# SCH_6_Channel_Energy_Monitor_17-09-2023_.net
KiCad netlist of a schematic drawn in EasyEDA
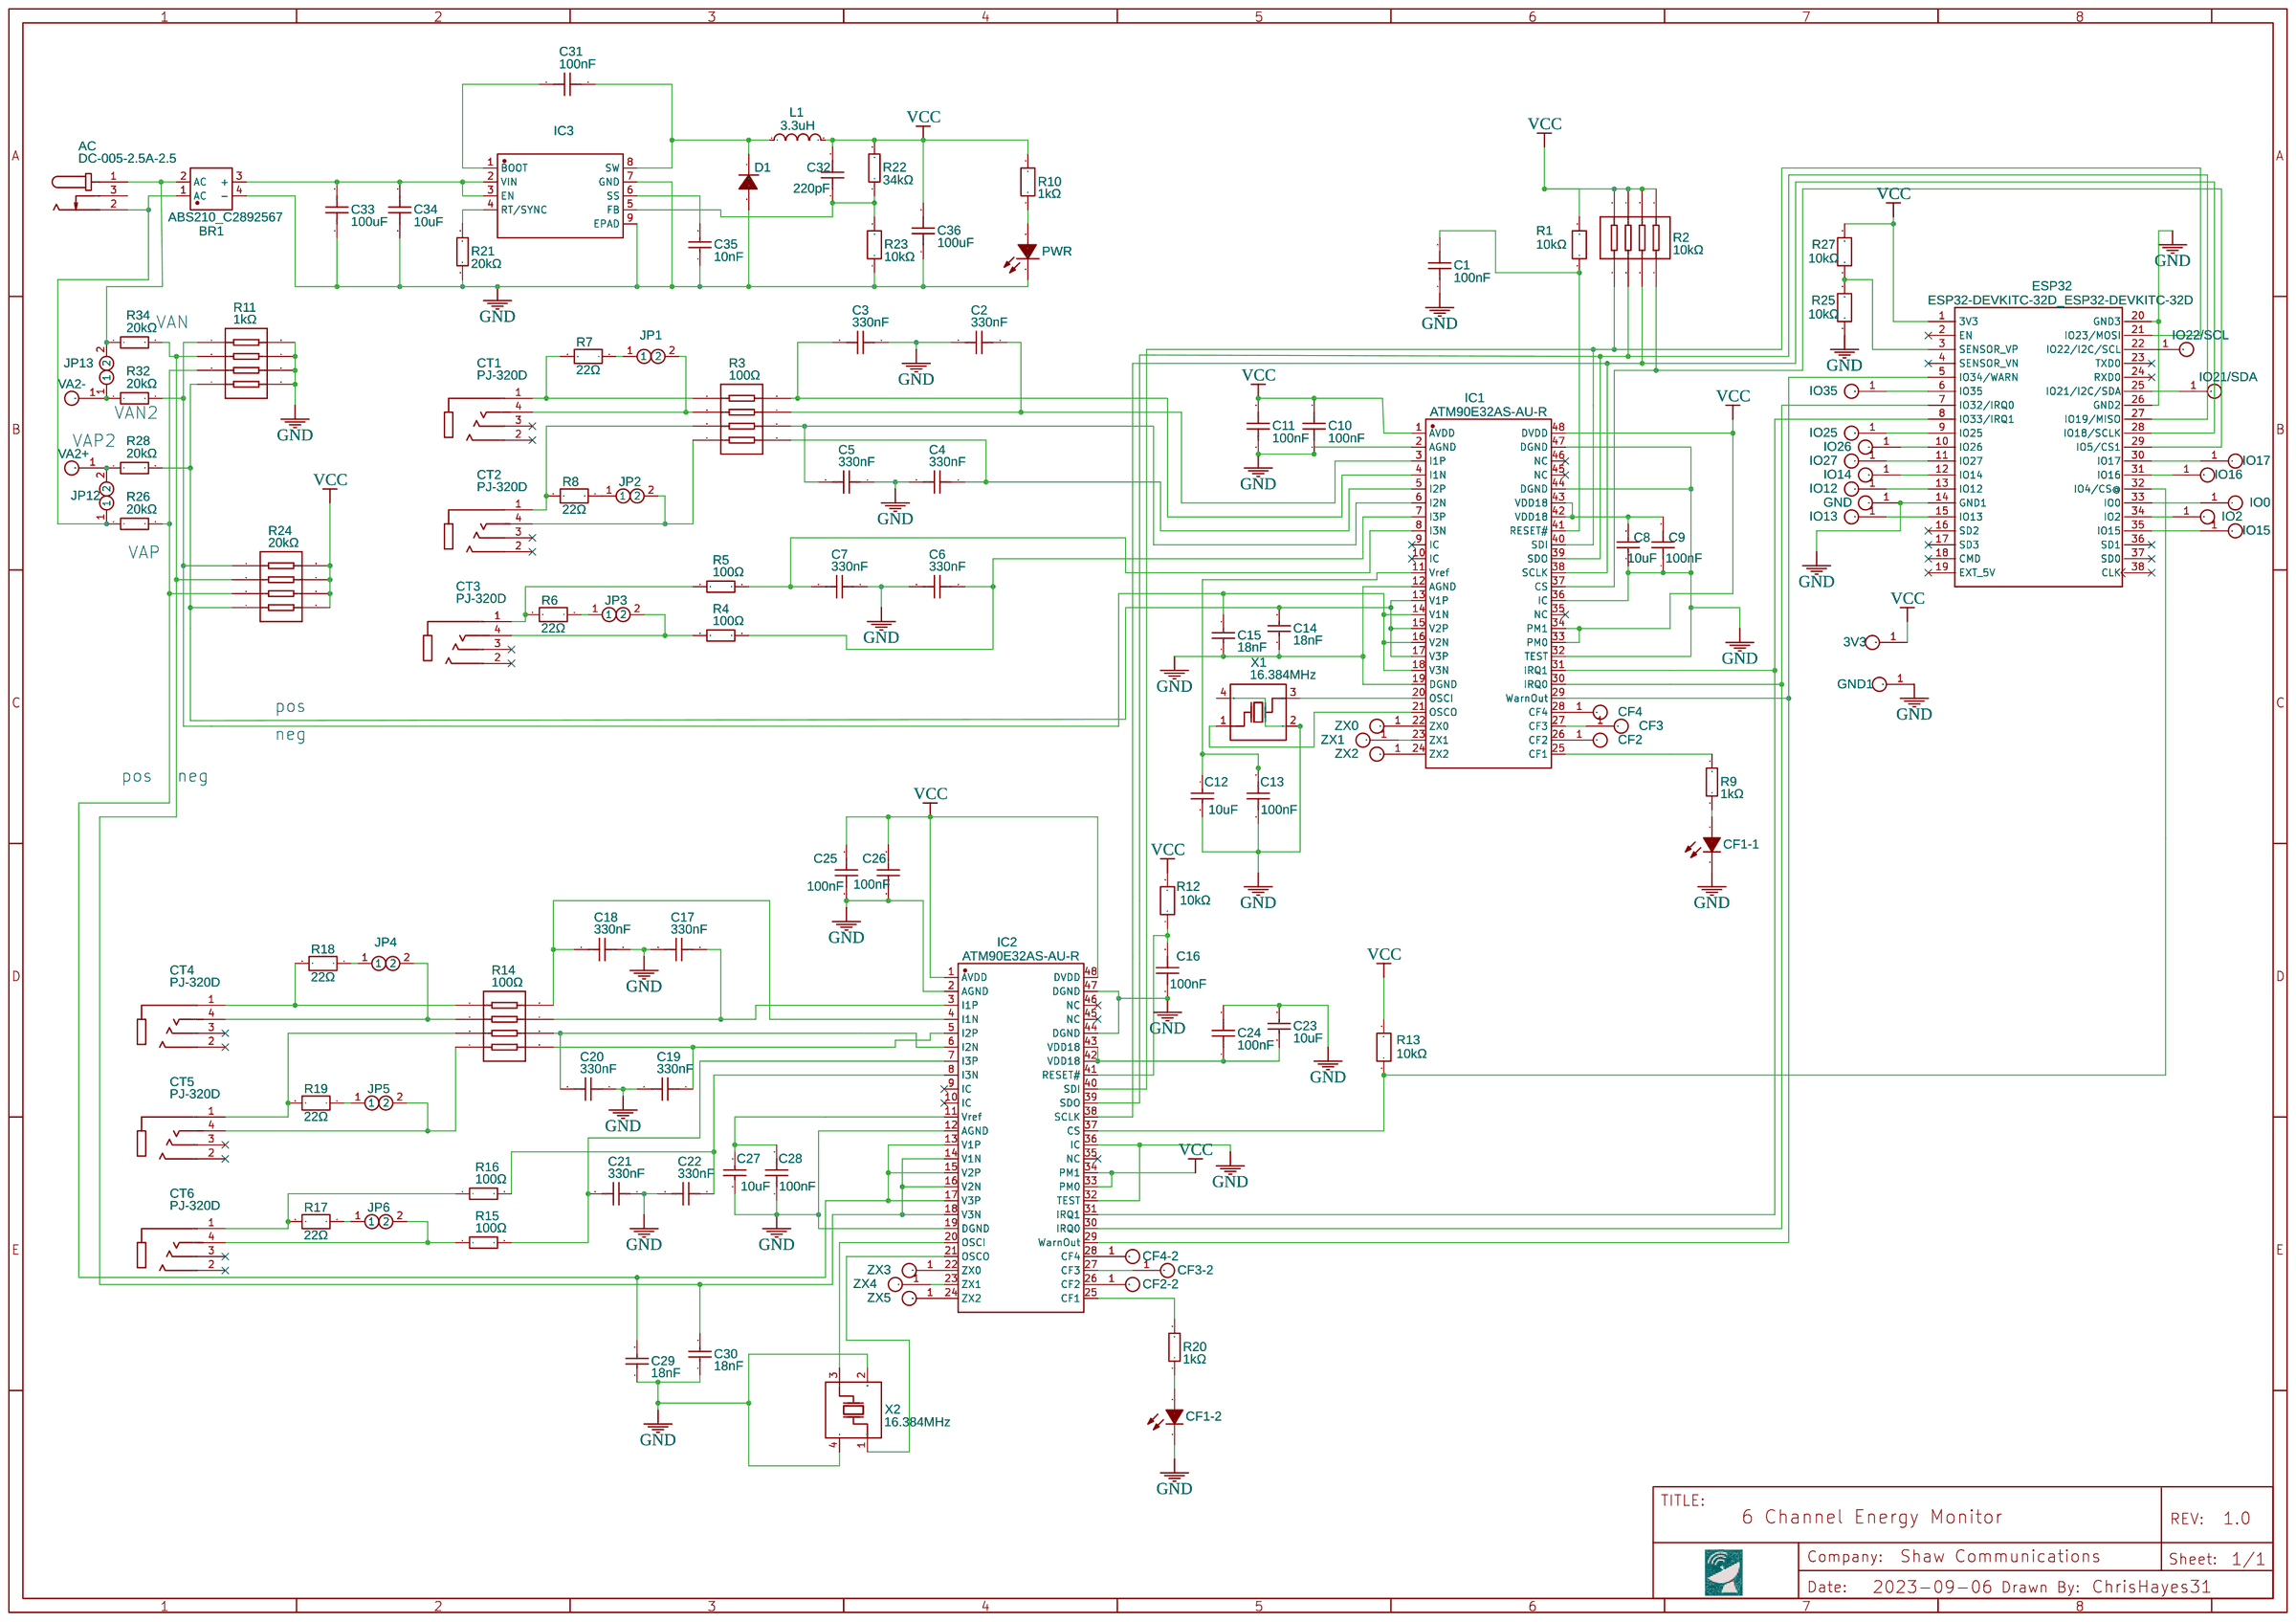
[diagram p0: schematic sheet]

(export (version "E")
  (design (tool "Eeschema 10.0.6"))
  (components
    (comp (ref "3V3") (value "PAD-ROUND") (libsource (lib "") (part "PAD-ROUND_12")))
    (comp (ref "AC")
      (value "DC-005-2.5A-2.5")
      (fields (field (name "Manufacturer") "XKB Enterprise"))
      (libsource (lib "") (part "DC-005-2.5A-2.5"))
    )
    (comp (ref "BR1")
      (value "ABS210_C2892567")
      (fields (field (name "Manufacturer Part") "ABS210") (field (name "Manufacturer") "YONGYUTAI(永裕泰)"))
      (libsource (lib "") (part "ABS210_C2892567"))
    )
    (comp (ref "C1")
      (value "100nF")
      (fields (field (name "Manufacturer Part") "CGJ4J2X7R1E104K125AA") (field (name "Manufacturer") "TDK"))
      (libsource (lib "") (part "CGJ4J2X7R1E104K125AA"))
    )
    (comp (ref "C2")
      (value "330nF")
      (fields
        (field (name "Manufacturer Part") "TCC0805X7R334K500DT")
        (field (name "Manufacturer") "CCTC(三环)")
      )
      (libsource (lib "") (part "TCC0805X7R334K500DT"))
    )
    (comp (ref "C3")
      (value "330nF")
      (fields
        (field (name "Manufacturer Part") "TCC0805X7R334K500DT")
        (field (name "Manufacturer") "CCTC(三环)")
      )
      (libsource (lib "") (part "TCC0805X7R334K500DT"))
    )
    (comp (ref "C4")
      (value "330nF")
      (fields
        (field (name "Manufacturer Part") "TCC0805X7R334K500DT")
        (field (name "Manufacturer") "CCTC(三环)")
      )
      (libsource (lib "") (part "TCC0805X7R334K500DT"))
    )
    (comp (ref "C5")
      (value "330nF")
      (fields
        (field (name "Manufacturer Part") "TCC0805X7R334K500DT")
        (field (name "Manufacturer") "CCTC(三环)")
      )
      (libsource (lib "") (part "TCC0805X7R334K500DT"))
    )
    (comp (ref "C6")
      (value "330nF")
      (fields
        (field (name "Manufacturer Part") "TCC0805X7R334K500DT")
        (field (name "Manufacturer") "CCTC(三环)")
      )
      (libsource (lib "") (part "TCC0805X7R334K500DT"))
    )
    (comp (ref "C7")
      (value "330nF")
      (fields
        (field (name "Manufacturer Part") "TCC0805X7R334K500DT")
        (field (name "Manufacturer") "CCTC(三环)")
      )
      (libsource (lib "") (part "TCC0805X7R334K500DT"))
    )
    (comp (ref "C8")
      (value "10uF")
      (fields
        (field (name "Manufacturer Part") "CC0805KKX5R8BB106")
        (field (name "Manufacturer") "YAGEO(国巨)")
      )
      (libsource (lib "") (part "CC0805KKX5R8BB106_1"))
    )
    (comp (ref "C9")
      (value "100nF")
      (fields (field (name "Manufacturer Part") "CGJ4J2X7R1E104K125AA") (field (name "Manufacturer") "TDK"))
      (libsource (lib "") (part "CGJ4J2X7R1E104K125AA"))
    )
    (comp (ref "C10")
      (value "100nF")
      (fields (field (name "Manufacturer Part") "CGJ4J2X7R1E104K125AA") (field (name "Manufacturer") "TDK"))
      (libsource (lib "") (part "CGJ4J2X7R1E104K125AA"))
    )
    (comp (ref "C11")
      (value "100nF")
      (fields (field (name "Manufacturer Part") "CGJ4J2X7R1E104K125AA") (field (name "Manufacturer") "TDK"))
      (libsource (lib "") (part "CGJ4J2X7R1E104K125AA"))
    )
    (comp (ref "C12")
      (value "10uF")
      (fields
        (field (name "Manufacturer Part") "CC0805KKX5R8BB106")
        (field (name "Manufacturer") "YAGEO(国巨)")
      )
      (libsource (lib "") (part "CC0805KKX5R8BB106"))
    )
    (comp (ref "C13")
      (value "100nF")
      (fields (field (name "Manufacturer Part") "CGJ4J2X7R1E104K125AA") (field (name "Manufacturer") "TDK"))
      (libsource (lib "") (part "CGJ4J2X7R1E104K125AA"))
    )
    (comp (ref "C14")
      (value "18nF")
      (fields
        (field (name "Manufacturer Part") "CC0805KRX7R9BB183")
        (field (name "Manufacturer") "YAGEO(国巨)")
      )
      (libsource (lib "") (part "CC0805KRX7R9BB183"))
    )
    (comp (ref "C15")
      (value "18nF")
      (fields
        (field (name "Manufacturer Part") "CC0805KRX7R9BB183")
        (field (name "Manufacturer") "YAGEO(国巨)")
      )
      (libsource (lib "") (part "CC0805KRX7R9BB183"))
    )
    (comp (ref "C16")
      (value "100nF")
      (fields (field (name "Manufacturer Part") "CGJ4J2X7R1E104K125AA") (field (name "Manufacturer") "TDK"))
      (libsource (lib "") (part "CGJ4J2X7R1E104K125AA"))
    )
    (comp (ref "C17")
      (value "330nF")
      (fields
        (field (name "Manufacturer Part") "TCC0805X7R334K500DT")
        (field (name "Manufacturer") "CCTC(三环)")
      )
      (libsource (lib "") (part "TCC0805X7R334K500DT"))
    )
    (comp (ref "C18")
      (value "330nF")
      (fields
        (field (name "Manufacturer Part") "TCC0805X7R334K500DT")
        (field (name "Manufacturer") "CCTC(三环)")
      )
      (libsource (lib "") (part "TCC0805X7R334K500DT"))
    )
    (comp (ref "C19")
      (value "330nF")
      (fields
        (field (name "Manufacturer Part") "TCC0805X7R334K500DT")
        (field (name "Manufacturer") "CCTC(三环)")
      )
      (libsource (lib "") (part "TCC0805X7R334K500DT"))
    )
    (comp (ref "C20")
      (value "330nF")
      (fields
        (field (name "Manufacturer Part") "TCC0805X7R334K500DT")
        (field (name "Manufacturer") "CCTC(三环)")
      )
      (libsource (lib "") (part "TCC0805X7R334K500DT"))
    )
    (comp (ref "C21")
      (value "330nF")
      (fields
        (field (name "Manufacturer Part") "TCC0805X7R334K500DT")
        (field (name "Manufacturer") "CCTC(三环)")
      )
      (libsource (lib "") (part "TCC0805X7R334K500DT"))
    )
    (comp (ref "C22")
      (value "330nF")
      (fields
        (field (name "Manufacturer Part") "TCC0805X7R334K500DT")
        (field (name "Manufacturer") "CCTC(三环)")
      )
      (libsource (lib "") (part "TCC0805X7R334K500DT"))
    )
    (comp (ref "C23")
      (value "10uF")
      (fields
        (field (name "Manufacturer Part") "CC0805KKX5R8BB106")
        (field (name "Manufacturer") "YAGEO(国巨)")
      )
      (libsource (lib "") (part "CC0805KKX5R8BB106_1"))
    )
    (comp (ref "C24")
      (value "100nF")
      (fields (field (name "Manufacturer Part") "CGJ4J2X7R1E104K125AA") (field (name "Manufacturer") "TDK"))
      (libsource (lib "") (part "CGJ4J2X7R1E104K125AA"))
    )
    (comp (ref "C25")
      (value "100nF")
      (fields (field (name "Manufacturer Part") "CGJ4J2X7R1E104K125AA") (field (name "Manufacturer") "TDK"))
      (libsource (lib "") (part "CGJ4J2X7R1E104K125AA"))
    )
    (comp (ref "C26")
      (value "100nF")
      (fields (field (name "Manufacturer Part") "CGJ4J2X7R1E104K125AA") (field (name "Manufacturer") "TDK"))
      (libsource (lib "") (part "CGJ4J2X7R1E104K125AA"))
    )
    (comp (ref "C27")
      (value "10uF")
      (fields
        (field (name "Manufacturer Part") "CC0805KKX5R8BB106")
        (field (name "Manufacturer") "YAGEO(国巨)")
      )
      (libsource (lib "") (part "CC0805KKX5R8BB106"))
    )
    (comp (ref "C28")
      (value "100nF")
      (fields (field (name "Manufacturer Part") "CGJ4J2X7R1E104K125AA") (field (name "Manufacturer") "TDK"))
      (libsource (lib "") (part "CGJ4J2X7R1E104K125AA"))
    )
    (comp (ref "C29")
      (value "18nF")
      (fields
        (field (name "Manufacturer Part") "CC0805KRX7R9BB183")
        (field (name "Manufacturer") "YAGEO(国巨)")
      )
      (libsource (lib "") (part "CC0805KRX7R9BB183"))
    )
    (comp (ref "C30")
      (value "18nF")
      (fields
        (field (name "Manufacturer Part") "CC0805KRX7R9BB183")
        (field (name "Manufacturer") "YAGEO(国巨)")
      )
      (libsource (lib "") (part "CC0805KRX7R9BB183"))
    )
    (comp (ref "C31")
      (value "100nF")
      (fields
        (field (name "Manufacturer Part") "CC0805JRX7R7BB104")
        (field (name "Manufacturer") "YAGEO(国巨)")
      )
      (libsource (lib "") (part "CC0805JRX7R7BB104"))
    )
    (comp (ref "C32")
      (value "220pF")
      (fields
        (field (name "Manufacturer Part") "CC0805JRNPO0BN221")
        (field (name "Manufacturer") "YAGEO(国巨)")
      )
      (libsource (lib "") (part "CC0805JRNPO0BN221"))
    )
    (comp (ref "C33")
      (value "100uF")
      (fields
        (field (name "Manufacturer Part") "GRM21BC80E107ME15L")
        (field (name "Manufacturer") "muRata(村田)")
      )
      (libsource (lib "") (part "GRM21BC80E107ME15L"))
    )
    (comp (ref "C34")
      (value "10uF")
      (fields
        (field (name "Manufacturer Part") "CC0805KKX7R7BB106")
        (field (name "Manufacturer") "YAGEO(国巨)")
      )
      (libsource (lib "") (part "CC0805KKX7R7BB106"))
    )
    (comp (ref "C35")
      (value "10nF")
      (fields
        (field (name "Manufacturer Part") "CC0805KKX7RBBB103")
        (field (name "Manufacturer") "YAGEO(国巨)")
      )
      (libsource (lib "") (part "CC0805KKX7RBBB103"))
    )
    (comp (ref "C36")
      (value "100uF")
      (fields
        (field (name "Manufacturer Part") "GRM21BC80E107ME15L")
        (field (name "Manufacturer") "muRata(村田)")
      )
      (libsource (lib "") (part "GRM21BC80E107ME15L"))
    )
    (comp (ref "CF1-1")
      (value "FC-DA1608BK-470H10")
      (fields (field (name "Manufacturer Part") "NCD0603B1") (field (name "Manufacturer") "国星光电"))
      (libsource (lib "") (part "FC-DA1608BK-470H10"))
    )
    (comp (ref "CF1-2")
      (value "FC-DA1608BK-470H10")
      (fields (field (name "Manufacturer Part") "NCD0603B1") (field (name "Manufacturer") "国星光电"))
      (libsource (lib "") (part "FC-DA1608BK-470H10"))
    )
    (comp (ref "CF2") (value "PAD-ROUND") (libsource (lib "") (part "PAD-ROUND_1")))
    (comp (ref "CF2-2") (value "PAD-ROUND") (libsource (lib "") (part "PAD-ROUND_11")))
    (comp (ref "CF3") (value "PAD-ROUND") (libsource (lib "") (part "PAD-ROUND_1")))
    (comp (ref "CF3-2") (value "PAD-ROUND") (libsource (lib "") (part "PAD-ROUND_8")))
    (comp (ref "CF4") (value "PAD-ROUND") (libsource (lib "") (part "PAD-ROUND_1")))
    (comp (ref "CF4-2") (value "PAD-ROUND") (libsource (lib "") (part "PAD-ROUND_10")))
    (comp (ref "CT1")
      (value "PJ-320D")
      (fields (field (name "Manufacturer") "SHOU HAN"))
      (libsource (lib "") (part "PJ-320D"))
    )
    (comp (ref "CT2")
      (value "PJ-320D")
      (fields (field (name "Manufacturer") "SHOU HAN"))
      (libsource (lib "") (part "PJ-320D"))
    )
    (comp (ref "CT3")
      (value "PJ-320D")
      (fields (field (name "Manufacturer") "SHOU HAN"))
      (libsource (lib "") (part "PJ-320D"))
    )
    (comp (ref "CT4")
      (value "PJ-320D")
      (fields (field (name "Manufacturer") "SHOU HAN"))
      (libsource (lib "") (part "PJ-320D"))
    )
    (comp (ref "CT5")
      (value "PJ-320D")
      (fields (field (name "Manufacturer") "SHOU HAN"))
      (libsource (lib "") (part "PJ-320D"))
    )
    (comp (ref "CT6")
      (value "PJ-320D")
      (fields (field (name "Manufacturer") "SHOU HAN"))
      (libsource (lib "") (part "PJ-320D"))
    )
    (comp (ref "D1")
      (value "M7_C95872")
      (fields (field (name "Manufacturer Part") "M7") (field (name "Manufacturer") "MDD"))
      (libsource (lib "") (part "M7_C95872"))
    )
    (comp (ref "ESP32")
      (value "ESP32-DEVKITC-32D_ESP32-DEVKITC-32D")
      (libsource (lib "") (part "ESP32-DEVKITC-32D_ESP32-DEVKITC-32D"))
    )
    (comp (ref "GND") (value "PAD-ROUND") (libsource (lib "") (part "PAD-ROUND_4")))
    (comp (ref "GND1") (value "PAD-ROUND") (libsource (lib "") (part "PAD-ROUND_4")))
    (comp (ref "IC1")
      (value "ATM90E32AS-AU-R")
      (fields (field (name "Manufacturer") "MICROCHIP(美国微芯)"))
      (libsource (lib "") (part "ATM90E32AS-AU-R"))
    )
    (comp (ref "IC2")
      (value "ATM90E32AS-AU-R")
      (fields (field (name "Manufacturer") "MICROCHIP(美国微芯)"))
      (libsource (lib "") (part "ATM90E32AS-AU-R"))
    )
    (comp (ref "IC3")
      (value "LMR14020SDDAR")
      (fields (field (name "Manufacturer") "TI(德州仪器)"))
      (libsource (lib "") (part "LMR14020SDDAR"))
    )
    (comp (ref "IO0") (value "PAD-ROUND") (libsource (lib "") (part "PAD-ROUND_2")))
    (comp (ref "IO2") (value "PAD-ROUND") (libsource (lib "") (part "PAD-ROUND_2")))
    (comp (ref "IO12") (value "PAD-ROUND") (libsource (lib "") (part "PAD-ROUND_5")))
    (comp (ref "IO13") (value "PAD-ROUND") (libsource (lib "") (part "PAD-ROUND_5")))
    (comp (ref "IO14") (value "PAD-ROUND") (libsource (lib "") (part "PAD-ROUND_5")))
    (comp (ref "IO15") (value "PAD-ROUND") (libsource (lib "") (part "PAD-ROUND_2")))
    (comp (ref "IO16") (value "PAD-ROUND") (libsource (lib "") (part "PAD-ROUND_2")))
    (comp (ref "IO17") (value "PAD-ROUND") (libsource (lib "") (part "PAD-ROUND_2")))
    (comp (ref "IO21/SDA") (value "PAD-ROUND") (libsource (lib "") (part "PAD-ROUND_3")))
    (comp (ref "IO22/SCL") (value "PAD-ROUND") (libsource (lib "") (part "PAD-ROUND_7")))
    (comp (ref "IO25") (value "PAD-ROUND") (libsource (lib "") (part "PAD-ROUND_5")))
    (comp (ref "IO26") (value "PAD-ROUND") (libsource (lib "") (part "PAD-ROUND_5")))
    (comp (ref "IO27") (value "PAD-ROUND") (libsource (lib "") (part "PAD-ROUND_5")))
    (comp (ref "IO35") (value "PAD-ROUND") (libsource (lib "") (part "PAD-ROUND_5")))
    (comp (ref "JP1") (value "J-pad soldering") (libsource (lib "") (part "J-pad soldering")))
    (comp (ref "JP2") (value "J-pad soldering") (libsource (lib "") (part "J-pad soldering")))
    (comp (ref "JP3") (value "J-pad soldering") (libsource (lib "") (part "J-pad soldering")))
    (comp (ref "JP4") (value "J-pad soldering") (libsource (lib "") (part "J-pad soldering")))
    (comp (ref "JP5") (value "J-pad soldering") (libsource (lib "") (part "J-pad soldering")))
    (comp (ref "JP6") (value "J-pad soldering") (libsource (lib "") (part "J-pad soldering")))
    (comp (ref "JP12") (value "J-pad soldering") (libsource (lib "") (part "J-pad soldering_1")))
    (comp (ref "JP13") (value "J-pad soldering") (libsource (lib "") (part "J-pad soldering_1")))
    (comp (ref "L1")
      (value "3.3uH")
      (fields (field (name "Manufacturer Part") "CYA0630-3.3UH") (field (name "Manufacturer") "SHOU HAN(首韩)"))
      (libsource (lib "") (part "CYA0630-3.3UH"))
    )
    (comp (ref "PWR")
      (value "EL0603/G6C-A01/DT(TS)(GW)")
      (fields (field (name "Manufacturer") "EVERLIGHT(亿光)"))
      (libsource (lib "") (part "EL0603/G6C-A01/DT(TS)(GW)"))
    )
    (comp (ref "R1")
      (value "10kΩ")
      (fields (field (name "Manufacturer Part") "SCR0805F10K") (field (name "Manufacturer") "VO(翔胜)"))
      (libsource (lib "") (part "SCR0805F10K"))
    )
    (comp (ref "R2")
      (value "10kΩ")
      (fields
        (field (name "Manufacturer Part") "4D03WGJ0103T5E")
        (field (name "Manufacturer") "UNI-ROYAL(厚声)")
      )
      (libsource (lib "") (part "4D03WGJ0103T5E"))
    )
    (comp (ref "R3")
      (value "100Ω")
      (fields
        (field (name "Manufacturer Part") "4D03WGJ0101T5E")
        (field (name "Manufacturer") "UNI-ROYAL(厚声)")
      )
      (libsource (lib "") (part "4D03WGJ0101T5E"))
    )
    (comp (ref "R4")
      (value "100Ω")
      (fields
        (field (name "Manufacturer Part") "0805W8F1000T5E")
        (field (name "Manufacturer") "UNI-ROYAL(厚声)")
      )
      (libsource (lib "") (part "0805W8F1000T5E"))
    )
    (comp (ref "R5")
      (value "100Ω")
      (fields
        (field (name "Manufacturer Part") "0805W8F1000T5E")
        (field (name "Manufacturer") "UNI-ROYAL(厚声)")
      )
      (libsource (lib "") (part "0805W8F1000T5E"))
    )
    (comp (ref "R6")
      (value "22Ω")
      (fields (field (name "Manufacturer Part") "SCR0805F22R") (field (name "Manufacturer") "VO(翔胜)"))
      (libsource (lib "") (part "SCR0805F22R"))
    )
    (comp (ref "R7")
      (value "22Ω")
      (fields (field (name "Manufacturer Part") "SCR0805F22R") (field (name "Manufacturer") "VO(翔胜)"))
      (libsource (lib "") (part "SCR0805F22R"))
    )
    (comp (ref "R8")
      (value "22Ω")
      (fields (field (name "Manufacturer Part") "SCR0805F22R") (field (name "Manufacturer") "VO(翔胜)"))
      (libsource (lib "") (part "SCR0805F22R"))
    )
    (comp (ref "R9")
      (value "1kΩ")
      (fields (field (name "Manufacturer Part") "CR0805F81001G") (field (name "Manufacturer") "LIZ(丽智电子)"))
      (libsource (lib "") (part "CR0805F81001G"))
    )
    (comp (ref "R10")
      (value "1kΩ")
      (fields (field (name "Manufacturer Part") "SCR0805F1K") (field (name "Manufacturer") "VO(翔胜)"))
      (libsource (lib "") (part "SCR0805F1K"))
    )
    (comp (ref "R11")
      (value "1kΩ")
      (fields
        (field (name "Manufacturer Part") "4D03WGJ0102T5E")
        (field (name "Manufacturer") "UNI-ROYAL(厚声)")
      )
      (libsource (lib "") (part "4D03WGJ0102T5E"))
    )
    (comp (ref "R12")
      (value "10kΩ")
      (fields (field (name "Manufacturer Part") "SCR0805F10K") (field (name "Manufacturer") "VO(翔胜)"))
      (libsource (lib "") (part "SCR0805F10K"))
    )
    (comp (ref "R13")
      (value "10kΩ")
      (fields (field (name "Manufacturer Part") "SCR0805F10K") (field (name "Manufacturer") "VO(翔胜)"))
      (libsource (lib "") (part "SCR0805F10K"))
    )
    (comp (ref "R14")
      (value "100Ω")
      (fields
        (field (name "Manufacturer Part") "4D03WGJ0101T5E")
        (field (name "Manufacturer") "UNI-ROYAL(厚声)")
      )
      (libsource (lib "") (part "4D03WGJ0101T5E"))
    )
    (comp (ref "R15")
      (value "100Ω")
      (fields
        (field (name "Manufacturer Part") "0805W8F1000T5E")
        (field (name "Manufacturer") "UNI-ROYAL(厚声)")
      )
      (libsource (lib "") (part "0805W8F1000T5E"))
    )
    (comp (ref "R16")
      (value "100Ω")
      (fields
        (field (name "Manufacturer Part") "0805W8F1000T5E")
        (field (name "Manufacturer") "UNI-ROYAL(厚声)")
      )
      (libsource (lib "") (part "0805W8F1000T5E"))
    )
    (comp (ref "R17")
      (value "22Ω")
      (fields (field (name "Manufacturer Part") "SCR0805F22R") (field (name "Manufacturer") "VO(翔胜)"))
      (libsource (lib "") (part "SCR0805F22R"))
    )
    (comp (ref "R18")
      (value "22Ω")
      (fields (field (name "Manufacturer Part") "SCR0805F22R") (field (name "Manufacturer") "VO(翔胜)"))
      (libsource (lib "") (part "SCR0805F22R"))
    )
    (comp (ref "R19")
      (value "22Ω")
      (fields (field (name "Manufacturer Part") "SCR0805F22R") (field (name "Manufacturer") "VO(翔胜)"))
      (libsource (lib "") (part "SCR0805F22R"))
    )
    (comp (ref "R20")
      (value "1kΩ")
      (fields (field (name "Manufacturer Part") "CR0805F81001G") (field (name "Manufacturer") "LIZ(丽智电子)"))
      (libsource (lib "") (part "CR0805F81001G"))
    )
    (comp (ref "R21")
      (value "20kΩ")
      (fields
        (field (name "Manufacturer Part") "QR0805F20K0P05Z")
        (field (name "Manufacturer") "EVER OHMS(天二科技)")
      )
      (libsource (lib "") (part "QR0805F20KP05"))
    )
    (comp (ref "R22")
      (value "34kΩ")
      (fields (field (name "Manufacturer Part") "AC0805FR-0734KL") (field (name "Manufacturer") "YAGEO(国巨)"))
      (libsource (lib "") (part "AC0805FR-0734KL"))
    )
    (comp (ref "R23")
      (value "10kΩ")
      (fields
        (field (name "Manufacturer Part") "CR0805J10K0P05Z")
        (field (name "Manufacturer") "EVER OHMS(天二科技)")
      )
      (libsource (lib "") (part "CR0805J10K0P05Z"))
    )
    (comp (ref "R24")
      (value "20kΩ")
      (fields
        (field (name "Manufacturer Part") "4D03WGJ0203T5E")
        (field (name "Manufacturer") "UNI-ROYAL(厚声)")
      )
      (libsource (lib "") (part "4D03WGJ0203T5E"))
    )
    (comp (ref "R25")
      (value "10kΩ")
      (fields (field (name "Manufacturer Part") "SCR0805F10K") (field (name "Manufacturer") "VO(翔胜)"))
      (libsource (lib "") (part "SCR0805F10K"))
    )
    (comp (ref "R26")
      (value "20kΩ")
      (fields (field (name "Manufacturer Part") "RK73H2ATTD2002F") (field (name "Manufacturer") "KOA"))
      (libsource (lib "") (part "RK73H2ATTD2002F"))
    )
    (comp (ref "R27")
      (value "10kΩ")
      (fields (field (name "Manufacturer Part") "SCR0805F10K") (field (name "Manufacturer") "VO(翔胜)"))
      (libsource (lib "") (part "SCR0805F10K"))
    )
    (comp (ref "R28")
      (value "20kΩ")
      (fields (field (name "Manufacturer Part") "RK73H2ATTD2002F") (field (name "Manufacturer") "KOA"))
      (libsource (lib "") (part "RK73H2ATTD2002F"))
    )
    (comp (ref "R32")
      (value "20kΩ")
      (fields (field (name "Manufacturer Part") "RK73H2ATTD2002F") (field (name "Manufacturer") "KOA"))
      (libsource (lib "") (part "RK73H2ATTD2002F"))
    )
    (comp (ref "R34")
      (value "20kΩ")
      (fields (field (name "Manufacturer Part") "RK73H2ATTD2002F") (field (name "Manufacturer") "KOA"))
      (libsource (lib "") (part "RK73H2ATTD2002F"))
    )
    (comp (ref "VA2+") (value "PAD-ROUND") (libsource (lib "") (part "PAD-ROUND_9")))
    (comp (ref "VA2-") (value "PAD-ROUND") (libsource (lib "") (part "PAD-ROUND_6")))
    (comp (ref "X1")
      (value "16.384MHz")
      (fields (field (name "Manufacturer Part") "X322516384MSB4SI") (field (name "Manufacturer") "YXC(扬兴晶振)"))
      (libsource (lib "") (part "X322516384MSB4SI"))
    )
    (comp (ref "X2")
      (value "16.384MHz")
      (fields (field (name "Manufacturer Part") "X322516384MSB4SI") (field (name "Manufacturer") "YXC(扬兴晶振)"))
      (libsource (lib "") (part "X322516384MSB4SI_1"))
    )
    (comp (ref "ZX0") (value "PAD-ROUND") (libsource (lib "") (part "PAD-ROUND")))
    (comp (ref "ZX1") (value "PAD-ROUND") (libsource (lib "") (part "PAD-ROUND")))
    (comp (ref "ZX2") (value "PAD-ROUND") (libsource (lib "") (part "PAD-ROUND")))
    (comp (ref "ZX3") (value "PAD-ROUND") (libsource (lib "") (part "PAD-ROUND")))
    (comp (ref "ZX4") (value "PAD-ROUND") (libsource (lib "") (part "PAD-ROUND")))
    (comp (ref "ZX5") (value "PAD-ROUND") (libsource (lib "") (part "PAD-ROUND")))
  )
  (nets
    (net (code "1") (name "GND") (class "Default")
      (node (ref "BR1") (pin "4") (pinfunction "-_4") (pintype "unspecified"))
      (node (ref "C1") (pin "1") (pinfunction "1_1") (pintype "unspecified"))
      (node (ref "C10") (pin "1") (pinfunction "1_1") (pintype "unspecified"))
      (node (ref "C11") (pin "1") (pinfunction "1_1") (pintype "unspecified"))
      (node (ref "C12") (pin "2") (pinfunction "2_2") (pintype "input"))
      (node (ref "C13") (pin "1") (pinfunction "1_1") (pintype "unspecified"))
      (node (ref "C14") (pin "1") (pinfunction "1_1") (pintype "input"))
      (node (ref "C15") (pin "1") (pinfunction "1_1") (pintype "input"))
      (node (ref "C16") (pin "1") (pinfunction "1_1") (pintype "unspecified"))
      (node (ref "C17") (pin "2") (pinfunction "2_2") (pintype "unspecified"))
      (node (ref "C18") (pin "1") (pinfunction "1_1") (pintype "unspecified"))
      (node (ref "C19") (pin "2") (pinfunction "2_2") (pintype "unspecified"))
      (node (ref "C2") (pin "2") (pinfunction "2_2") (pintype "unspecified"))
      (node (ref "C20") (pin "1") (pinfunction "1_1") (pintype "unspecified"))
      (node (ref "C21") (pin "1") (pinfunction "1_1") (pintype "unspecified"))
      (node (ref "C22") (pin "2") (pinfunction "2_2") (pintype "unspecified"))
      (node (ref "C23") (pin "2") (pinfunction "2_2") (pintype "input"))
      (node (ref "C24") (pin "2") (pinfunction "2_2") (pintype "unspecified"))
      (node (ref "C25") (pin "1") (pinfunction "1_1") (pintype "unspecified"))
      (node (ref "C26") (pin "1") (pinfunction "1_1") (pintype "unspecified"))
      (node (ref "C27") (pin "2") (pinfunction "2_2") (pintype "input"))
      (node (ref "C28") (pin "1") (pinfunction "1_1") (pintype "unspecified"))
      (node (ref "C29") (pin "1") (pinfunction "1_1") (pintype "input"))
      (node (ref "C3") (pin "1") (pinfunction "1_1") (pintype "unspecified"))
      (node (ref "C30") (pin "1") (pinfunction "1_1") (pintype "input"))
      (node (ref "C33") (pin "1") (pinfunction "1_1") (pintype "unspecified"))
      (node (ref "C34") (pin "2") (pinfunction "2_2") (pintype "unspecified"))
      (node (ref "C35") (pin "1") (pinfunction "1_1") (pintype "input"))
      (node (ref "C36") (pin "1") (pinfunction "1_1") (pintype "unspecified"))
      (node (ref "C4") (pin "2") (pinfunction "2_2") (pintype "unspecified"))
      (node (ref "C5") (pin "1") (pinfunction "1_1") (pintype "unspecified"))
      (node (ref "C6") (pin "2") (pinfunction "2_2") (pintype "unspecified"))
      (node (ref "C7") (pin "1") (pinfunction "1_1") (pintype "unspecified"))
      (node (ref "C8") (pin "1") (pinfunction "1_1") (pintype "input"))
      (node (ref "C9") (pin "1") (pinfunction "1_1") (pintype "unspecified"))
      (node (ref "CF1-1") (pin "1") (pinfunction "-_1") (pintype "input"))
      (node (ref "CF1-2") (pin "1") (pinfunction "-_1") (pintype "input"))
      (node (ref "D1") (pin "2") (pinfunction "A_2") (pintype "unspecified"))
      (node (ref "ESP32") (pin "14") (pinfunction "GND1_14") (pintype "bidirectional"))
      (node (ref "ESP32") (pin "20") (pinfunction "GND3_20") (pintype "bidirectional"))
      (node (ref "ESP32") (pin "26") (pinfunction "GND2_26") (pintype "bidirectional"))
      (node (ref "GND") (pin "1") (pinfunction "Pad_1") (pintype "unspecified"))
      (node (ref "GND1") (pin "1") (pinfunction "Pad_1") (pintype "unspecified"))
      (node (ref "IC1") (pin "12") (pinfunction "AGND_12") (pintype "unspecified"))
      (node (ref "IC1") (pin "19") (pinfunction "DGND_19") (pintype "unspecified"))
      (node (ref "IC1") (pin "2") (pinfunction "AGND_2") (pintype "unspecified"))
      (node (ref "IC1") (pin "32") (pinfunction "TEST_32") (pintype "unspecified"))
      (node (ref "IC1") (pin "36") (pinfunction "IC_36") (pintype "unspecified"))
      (node (ref "IC1") (pin "44") (pinfunction "DGND_44") (pintype "unspecified"))
      (node (ref "IC1") (pin "47") (pinfunction "DGND_47") (pintype "unspecified"))
      (node (ref "IC2") (pin "12") (pinfunction "AGND_12") (pintype "unspecified"))
      (node (ref "IC2") (pin "19") (pinfunction "DGND_19") (pintype "unspecified"))
      (node (ref "IC2") (pin "2") (pinfunction "AGND_2") (pintype "unspecified"))
      (node (ref "IC2") (pin "32") (pinfunction "TEST_32") (pintype "unspecified"))
      (node (ref "IC2") (pin "36") (pinfunction "IC_36") (pintype "unspecified"))
      (node (ref "IC2") (pin "44") (pinfunction "DGND_44") (pintype "unspecified"))
      (node (ref "IC2") (pin "47") (pinfunction "DGND_47") (pintype "unspecified"))
      (node (ref "IC3") (pin "7") (pinfunction "GND_7") (pintype "unspecified"))
      (node (ref "IC3") (pin "9") (pinfunction "EPAD_9") (pintype "unspecified"))
      (node (ref "PWR") (pin "2") (pinfunction "K_2") (pintype "unspecified"))
      (node (ref "R11") (pin "5") (pinfunction "5_5") (pintype "input"))
      (node (ref "R11") (pin "6") (pinfunction "6_6") (pintype "input"))
      (node (ref "R11") (pin "7") (pinfunction "7_7") (pintype "input"))
      (node (ref "R11") (pin "8") (pinfunction "8_8") (pintype "input"))
      (node (ref "R21") (pin "1") (pinfunction "1_1") (pintype "unspecified"))
      (node (ref "R23") (pin "1") (pinfunction "1_1") (pintype "unspecified"))
      (node (ref "R25") (pin "1") (pinfunction "1_1") (pintype "unspecified"))
      (node (ref "X1") (pin "2") (pinfunction "GND_2") (pintype "unspecified"))
      (node (ref "X1") (pin "4") (pinfunction "GND_4") (pintype "unspecified"))
      (node (ref "X2") (pin "2") (pinfunction "GND_2") (pintype "unspecified"))
      (node (ref "X2") (pin "4") (pinfunction "GND_4") (pintype "unspecified"))
    )
    (net (code "2") (name "Net-(AC-Pad1)") (class "Default")
      (node (ref "AC") (pin "1") (pinfunction "1_1") (pintype "unspecified"))
      (node (ref "BR1") (pin "2") (pinfunction "AC_2") (pintype "unspecified"))
      (node (ref "JP13") (pin "2") (pinfunction "2_2") (pintype "unspecified"))
      (node (ref "R34") (pin "1") (pinfunction "1_1") (pintype "unspecified"))
    )
    (net (code "3") (name "Net-(AC-Pad2)") (class "Default")
      (node (ref "AC") (pin "2") (pinfunction "2_2") (pintype "unspecified"))
      (node (ref "BR1") (pin "1") (pinfunction "AC_1") (pintype "unspecified"))
      (node (ref "JP12") (pin "1") (pinfunction "1_1") (pintype "unspecified"))
      (node (ref "R26") (pin "1") (pinfunction "1_1") (pintype "unspecified"))
    )
    (net (code "4") (name "Net-(BR1-+)") (class "Default")
      (node (ref "BR1") (pin "3") (pinfunction "+_3") (pintype "unspecified"))
      (node (ref "C33") (pin "2") (pinfunction "2_2") (pintype "unspecified"))
      (node (ref "C34") (pin "1") (pinfunction "1_1") (pintype "unspecified"))
      (node (ref "IC3") (pin "2") (pinfunction "VIN_2") (pintype "unspecified"))
      (node (ref "IC3") (pin "3") (pinfunction "EN_3") (pintype "unspecified"))
    )
    (net (code "5") (name "Net-(C8-Pad2)") (class "Default")
      (node (ref "C8") (pin "2") (pinfunction "2_2") (pintype "input"))
      (node (ref "C9") (pin "2") (pinfunction "2_2") (pintype "unspecified"))
      (node (ref "IC1") (pin "42") (pinfunction "VDD18_42") (pintype "unspecified"))
      (node (ref "IC1") (pin "43") (pinfunction "VDD18_43") (pintype "unspecified"))
    )
    (net (code "6") (name "Net-(C23-Pad1)") (class "Default")
      (node (ref "C23") (pin "1") (pinfunction "1_1") (pintype "input"))
      (node (ref "C24") (pin "1") (pinfunction "1_1") (pintype "unspecified"))
      (node (ref "IC2") (pin "42") (pinfunction "VDD18_42") (pintype "unspecified"))
      (node (ref "IC2") (pin "43") (pinfunction "VDD18_43") (pintype "unspecified"))
    )
    (net (code "7") (name "Net-(CF1-1-+)") (class "Default")
      (node (ref "CF1-1") (pin "2") (pinfunction "+_2") (pintype "input"))
      (node (ref "R9") (pin "1") (pinfunction "1_1") (pintype "input"))
    )
    (net (code "8") (name "Net-(CF1-2-+)") (class "Default")
      (node (ref "CF1-2") (pin "2") (pinfunction "+_2") (pintype "input"))
      (node (ref "R20") (pin "1") (pinfunction "1_1") (pintype "input"))
    )
    (net (code "9") (name "Net-(CT1-Pad1)") (class "Default")
      (node (ref "CT1") (pin "1") (pinfunction "1_1") (pintype "unspecified"))
      (node (ref "R3") (pin "1") (pinfunction "1_1") (pintype "input"))
      (node (ref "R7") (pin "2") (pinfunction "2_2") (pintype "unspecified"))
    )
    (net (code "10") (name "Net-(CT1-Pad4)") (class "Default")
      (node (ref "CT1") (pin "4") (pinfunction "4_4") (pintype "unspecified"))
      (node (ref "JP1") (pin "2") (pinfunction "2_2") (pintype "unspecified"))
      (node (ref "R3") (pin "2") (pinfunction "2_2") (pintype "input"))
    )
    (net (code "11") (name "Net-(CT2-Pad1)") (class "Default")
      (node (ref "CT2") (pin "1") (pinfunction "1_1") (pintype "unspecified"))
      (node (ref "R3") (pin "3") (pinfunction "3_3") (pintype "input"))
      (node (ref "R8") (pin "2") (pinfunction "2_2") (pintype "unspecified"))
    )
    (net (code "12") (name "Net-(CT2-Pad4)") (class "Default")
      (node (ref "CT2") (pin "4") (pinfunction "4_4") (pintype "unspecified"))
      (node (ref "JP2") (pin "2") (pinfunction "2_2") (pintype "unspecified"))
      (node (ref "R3") (pin "4") (pinfunction "4_4") (pintype "input"))
    )
    (net (code "13") (name "Net-(CT3-Pad1)") (class "Default")
      (node (ref "CT3") (pin "1") (pinfunction "1_1") (pintype "unspecified"))
      (node (ref "R5") (pin "1") (pinfunction "1_1") (pintype "input"))
      (node (ref "R6") (pin "2") (pinfunction "2_2") (pintype "unspecified"))
    )
    (net (code "14") (name "Net-(CT3-Pad4)") (class "Default")
      (node (ref "CT3") (pin "4") (pinfunction "4_4") (pintype "unspecified"))
      (node (ref "JP3") (pin "2") (pinfunction "2_2") (pintype "unspecified"))
      (node (ref "R4") (pin "1") (pinfunction "1_1") (pintype "input"))
    )
    (net (code "15") (name "Net-(CT4-Pad1)") (class "Default")
      (node (ref "CT4") (pin "1") (pinfunction "1_1") (pintype "unspecified"))
      (node (ref "R14") (pin "1") (pinfunction "1_1") (pintype "input"))
      (node (ref "R18") (pin "2") (pinfunction "2_2") (pintype "unspecified"))
    )
    (net (code "16") (name "Net-(CT4-Pad4)") (class "Default")
      (node (ref "CT4") (pin "4") (pinfunction "4_4") (pintype "unspecified"))
      (node (ref "JP4") (pin "2") (pinfunction "2_2") (pintype "unspecified"))
      (node (ref "R14") (pin "2") (pinfunction "2_2") (pintype "input"))
    )
    (net (code "17") (name "Net-(CT5-Pad1)") (class "Default")
      (node (ref "CT5") (pin "1") (pinfunction "1_1") (pintype "unspecified"))
      (node (ref "R14") (pin "3") (pinfunction "3_3") (pintype "input"))
      (node (ref "R19") (pin "2") (pinfunction "2_2") (pintype "unspecified"))
    )
    (net (code "18") (name "Net-(CT5-Pad4)") (class "Default")
      (node (ref "CT5") (pin "4") (pinfunction "4_4") (pintype "unspecified"))
      (node (ref "JP5") (pin "2") (pinfunction "2_2") (pintype "unspecified"))
      (node (ref "R14") (pin "4") (pinfunction "4_4") (pintype "input"))
    )
    (net (code "19") (name "Net-(CT6-Pad1)") (class "Default")
      (node (ref "CT6") (pin "1") (pinfunction "1_1") (pintype "unspecified"))
      (node (ref "R16") (pin "1") (pinfunction "1_1") (pintype "input"))
      (node (ref "R17") (pin "2") (pinfunction "2_2") (pintype "unspecified"))
    )
    (net (code "20") (name "Net-(CT6-Pad4)") (class "Default")
      (node (ref "CT6") (pin "4") (pinfunction "4_4") (pintype "unspecified"))
      (node (ref "JP6") (pin "2") (pinfunction "2_2") (pintype "unspecified"))
      (node (ref "R15") (pin "1") (pinfunction "1_1") (pintype "input"))
    )
    (net (code "21") (name "Net-(D1-K)") (class "Default")
      (node (ref "C31") (pin "1") (pinfunction "1_1") (pintype "unspecified"))
      (node (ref "D1") (pin "1") (pinfunction "K_1") (pintype "unspecified"))
      (node (ref "IC3") (pin "8") (pinfunction "SW_8") (pintype "unspecified"))
      (node (ref "L1") (pin "1") (pinfunction "1_1") (pintype "unspecified"))
    )
    (net (code "22") (name "Net-(ESP32-IO0)") (class "Default")
      (node (ref "ESP32") (pin "33") (pinfunction "IO0_33") (pintype "bidirectional"))
      (node (ref "IO0") (pin "1") (pinfunction "Pad_1") (pintype "unspecified"))
    )
    (net (code "23") (name "Net-(ESP32-IO2)") (class "Default")
      (node (ref "ESP32") (pin "34") (pinfunction "IO2_34") (pintype "bidirectional"))
      (node (ref "IO2") (pin "1") (pinfunction "Pad_1") (pintype "unspecified"))
    )
    (net (code "24") (name "Net-(ESP32-IO4{slash}CS@)") (class "Default")
      (node (ref "ESP32") (pin "32") (pinfunction "IO4/CS@_32") (pintype "bidirectional"))
      (node (ref "IC2") (pin "37") (pinfunction "CS_37") (pintype "unspecified"))
      (node (ref "R13") (pin "1") (pinfunction "1_1") (pintype "unspecified"))
    )
    (net (code "25") (name "Net-(ESP32-IO5{slash}CS1)") (class "Default")
      (node (ref "ESP32") (pin "29") (pinfunction "IO5/CS1_29") (pintype "bidirectional"))
      (node (ref "IC1") (pin "37") (pinfunction "CS_37") (pintype "unspecified"))
      (node (ref "R2") (pin "4") (pinfunction "4_4") (pintype "input"))
    )
    (net (code "26") (name "Net-(ESP32-IO12)") (class "Default")
      (node (ref "ESP32") (pin "13") (pinfunction "IO12_13") (pintype "bidirectional"))
      (node (ref "IO12") (pin "1") (pinfunction "Pad_1") (pintype "unspecified"))
    )
    (net (code "27") (name "Net-(ESP32-IO13)") (class "Default")
      (node (ref "ESP32") (pin "15") (pinfunction "IO13_15") (pintype "bidirectional"))
      (node (ref "IO13") (pin "1") (pinfunction "Pad_1") (pintype "unspecified"))
    )
    (net (code "28") (name "Net-(ESP32-IO14)") (class "Default")
      (node (ref "ESP32") (pin "12") (pinfunction "IO14_12") (pintype "bidirectional"))
      (node (ref "IO14") (pin "1") (pinfunction "Pad_1") (pintype "unspecified"))
    )
    (net (code "29") (name "Net-(ESP32-IO15)") (class "Default")
      (node (ref "ESP32") (pin "35") (pinfunction "IO15_35") (pintype "bidirectional"))
      (node (ref "IO15") (pin "1") (pinfunction "Pad_1") (pintype "unspecified"))
    )
    (net (code "30") (name "Net-(ESP32-IO16)") (class "Default")
      (node (ref "ESP32") (pin "31") (pinfunction "IO16_31") (pintype "bidirectional"))
      (node (ref "IO16") (pin "1") (pinfunction "Pad_1") (pintype "unspecified"))
    )
    (net (code "31") (name "Net-(ESP32-IO17)") (class "Default")
      (node (ref "ESP32") (pin "30") (pinfunction "IO17_30") (pintype "bidirectional"))
      (node (ref "IO17") (pin "1") (pinfunction "Pad_1") (pintype "unspecified"))
    )
    (net (code "32") (name "Net-(ESP32-IO18{slash}SCLK)") (class "Default")
      (node (ref "ESP32") (pin "28") (pinfunction "IO18/SCLK_28") (pintype "bidirectional"))
      (node (ref "IC1") (pin "38") (pinfunction "SCLK_38") (pintype "unspecified"))
      (node (ref "IC2") (pin "38") (pinfunction "SCLK_38") (pintype "unspecified"))
      (node (ref "R2") (pin "3") (pinfunction "3_3") (pintype "input"))
    )
    (net (code "33") (name "Net-(ESP32-IO19{slash}MISO)") (class "Default")
      (node (ref "ESP32") (pin "27") (pinfunction "IO19/MISO_27") (pintype "bidirectional"))
      (node (ref "IC1") (pin "39") (pinfunction "SDO_39") (pintype "unspecified"))
      (node (ref "IC2") (pin "39") (pinfunction "SDO_39") (pintype "unspecified"))
      (node (ref "R2") (pin "2") (pinfunction "2_2") (pintype "input"))
    )
    (net (code "34") (name "Net-(ESP32-IO21{slash}I2C{slash}SDA)") (class "Default")
      (node (ref "ESP32") (pin "25") (pinfunction "IO21/I2C/SDA_25") (pintype "bidirectional"))
      (node (ref "IO21/SDA") (pin "1") (pinfunction "Pad_1") (pintype "unspecified"))
    )
    (net (code "35") (name "Net-(ESP32-IO22{slash}I2C{slash}SCL)") (class "Default")
      (node (ref "ESP32") (pin "22") (pinfunction "IO22/I2C/SCL_22") (pintype "bidirectional"))
      (node (ref "IO22/SCL") (pin "1") (pinfunction "Pad_1") (pintype "unspecified"))
    )
    (net (code "36") (name "Net-(ESP32-IO23{slash}MOSI)") (class "Default")
      (node (ref "ESP32") (pin "21") (pinfunction "IO23/MOSI_21") (pintype "bidirectional"))
      (node (ref "IC1") (pin "40") (pinfunction "SDI_40") (pintype "unspecified"))
      (node (ref "IC2") (pin "40") (pinfunction "SDI_40") (pintype "unspecified"))
      (node (ref "R2") (pin "1") (pinfunction "1_1") (pintype "input"))
    )
    (net (code "37") (name "Net-(ESP32-IO25)") (class "Default")
      (node (ref "ESP32") (pin "9") (pinfunction "IO25_9") (pintype "bidirectional"))
      (node (ref "IO25") (pin "1") (pinfunction "Pad_1") (pintype "unspecified"))
    )
    (net (code "38") (name "Net-(ESP32-IO26)") (class "Default")
      (node (ref "ESP32") (pin "10") (pinfunction "IO26_10") (pintype "bidirectional"))
      (node (ref "IO26") (pin "1") (pinfunction "Pad_1") (pintype "unspecified"))
    )
    (net (code "39") (name "Net-(ESP32-IO27)") (class "Default")
      (node (ref "ESP32") (pin "11") (pinfunction "IO27_11") (pintype "bidirectional"))
      (node (ref "IO27") (pin "1") (pinfunction "Pad_1") (pintype "unspecified"))
    )
    (net (code "40") (name "Net-(ESP32-IO32{slash}IRQ0)") (class "Default")
      (node (ref "ESP32") (pin "7") (pinfunction "IO32/IRQ0_7") (pintype "bidirectional"))
      (node (ref "IC1") (pin "30") (pinfunction "IRQ0_30") (pintype "unspecified"))
      (node (ref "IC2") (pin "30") (pinfunction "IRQ0_30") (pintype "unspecified"))
    )
    (net (code "41") (name "Net-(ESP32-IO33{slash}IRQ1)") (class "Default")
      (node (ref "ESP32") (pin "8") (pinfunction "IO33/IRQ1_8") (pintype "bidirectional"))
      (node (ref "IC1") (pin "31") (pinfunction "IRQ1_31") (pintype "unspecified"))
      (node (ref "IC2") (pin "31") (pinfunction "IRQ1_31") (pintype "unspecified"))
    )
    (net (code "42") (name "Net-(ESP32-IO34{slash}WARN)") (class "Default")
      (node (ref "ESP32") (pin "5") (pinfunction "IO34/WARN_5") (pintype "bidirectional"))
      (node (ref "IC1") (pin "29") (pinfunction "WarnOut_29") (pintype "unspecified"))
      (node (ref "IC2") (pin "29") (pinfunction "WarnOut_29") (pintype "unspecified"))
    )
    (net (code "43") (name "Net-(ESP32-IO35)") (class "Default")
      (node (ref "ESP32") (pin "6") (pinfunction "IO35_6") (pintype "bidirectional"))
      (node (ref "IO35") (pin "1") (pinfunction "Pad_1") (pintype "unspecified"))
    )
    (net (code "44") (name "Net-(ESP32-SENSOR_VP)") (class "Default")
      (node (ref "ESP32") (pin "3") (pinfunction "SENSOR_VP_3") (pintype "bidirectional"))
      (node (ref "R25") (pin "2") (pinfunction "2_2") (pintype "unspecified"))
      (node (ref "R27") (pin "1") (pinfunction "1_1") (pintype "unspecified"))
    )
    (net (code "45") (name "Net-(IC1-CF1)") (class "Default")
      (node (ref "IC1") (pin "25") (pinfunction "CF1_25") (pintype "unspecified"))
      (node (ref "R9") (pin "2") (pinfunction "2_2") (pintype "input"))
    )
    (net (code "46") (name "Net-(IC1-CF2)") (class "Default")
      (node (ref "CF2") (pin "1") (pinfunction "Pad_1") (pintype "unspecified"))
      (node (ref "IC1") (pin "26") (pinfunction "CF2_26") (pintype "unspecified"))
    )
    (net (code "47") (name "Net-(IC1-CF3)") (class "Default")
      (node (ref "CF3") (pin "1") (pinfunction "Pad_1") (pintype "unspecified"))
      (node (ref "IC1") (pin "27") (pinfunction "CF3_27") (pintype "unspecified"))
    )
    (net (code "48") (name "Net-(IC1-CF4)") (class "Default")
      (node (ref "CF4") (pin "1") (pinfunction "Pad_1") (pintype "unspecified"))
      (node (ref "IC1") (pin "28") (pinfunction "CF4_28") (pintype "unspecified"))
    )
    (net (code "49") (name "Net-(IC1-I1N)") (class "Default")
      (node (ref "C3") (pin "2") (pinfunction "2_2") (pintype "unspecified"))
      (node (ref "IC1") (pin "4") (pinfunction "I1N_4") (pintype "unspecified"))
      (node (ref "R3") (pin "8") (pinfunction "8_8") (pintype "input"))
    )
    (net (code "50") (name "Net-(IC1-I1P)") (class "Default")
      (node (ref "C2") (pin "1") (pinfunction "1_1") (pintype "unspecified"))
      (node (ref "IC1") (pin "3") (pinfunction "I1P_3") (pintype "unspecified"))
      (node (ref "R3") (pin "7") (pinfunction "7_7") (pintype "input"))
    )
    (net (code "51") (name "Net-(IC1-I2N)") (class "Default")
      (node (ref "C5") (pin "2") (pinfunction "2_2") (pintype "unspecified"))
      (node (ref "IC1") (pin "6") (pinfunction "I2N_6") (pintype "unspecified"))
      (node (ref "R3") (pin "6") (pinfunction "6_6") (pintype "input"))
    )
    (net (code "52") (name "Net-(IC1-I2P)") (class "Default")
      (node (ref "C4") (pin "1") (pinfunction "1_1") (pintype "unspecified"))
      (node (ref "IC1") (pin "5") (pinfunction "I2P_5") (pintype "unspecified"))
      (node (ref "R3") (pin "5") (pinfunction "5_5") (pintype "input"))
    )
    (net (code "53") (name "Net-(IC1-I3N)") (class "Default")
      (node (ref "C7") (pin "2") (pinfunction "2_2") (pintype "unspecified"))
      (node (ref "IC1") (pin "8") (pinfunction "I3N_8") (pintype "unspecified"))
      (node (ref "R5") (pin "2") (pinfunction "2_2") (pintype "input"))
    )
    (net (code "54") (name "Net-(IC1-I3P)") (class "Default")
      (node (ref "C6") (pin "1") (pinfunction "1_1") (pintype "unspecified"))
      (node (ref "IC1") (pin "7") (pinfunction "I3P_7") (pintype "unspecified"))
      (node (ref "R4") (pin "2") (pinfunction "2_2") (pintype "input"))
    )
    (net (code "55") (name "Net-(IC1-OSCI)") (class "Default")
      (node (ref "IC1") (pin "20") (pinfunction "OSCI_20") (pintype "unspecified"))
      (node (ref "X1") (pin "3") (pinfunction "OSC2_3") (pintype "unspecified"))
    )
    (net (code "56") (name "Net-(IC1-OSCO)") (class "Default")
      (node (ref "IC1") (pin "21") (pinfunction "OSCO_21") (pintype "unspecified"))
      (node (ref "X1") (pin "1") (pinfunction "OSC1_1") (pintype "unspecified"))
    )
    (net (code "57") (name "Net-(IC1-RESET#)") (class "Default")
      (node (ref "C1") (pin "2") (pinfunction "2_2") (pintype "unspecified"))
      (node (ref "IC1") (pin "41") (pinfunction "RESET#_41") (pintype "unspecified"))
      (node (ref "R1") (pin "1") (pinfunction "1_1") (pintype "unspecified"))
    )
    (net (code "58") (name "Net-(IC1-V1N)") (class "Default")
      (node (ref "C15") (pin "2") (pinfunction "2_2") (pintype "input"))
      (node (ref "IC1") (pin "14") (pinfunction "V1N_14") (pintype "unspecified"))
      (node (ref "IC1") (pin "16") (pinfunction "V2N_16") (pintype "unspecified"))
      (node (ref "IC1") (pin "18") (pinfunction "V3N_18") (pintype "unspecified"))
      (node (ref "R11") (pin "1") (pinfunction "1_1") (pintype "input"))
      (node (ref "R24") (pin "1") (pinfunction "1_1") (pintype "input"))
      (node (ref "R32") (pin "2") (pinfunction "2_2") (pintype "unspecified"))
    )
    (net (code "59") (name "Net-(IC1-V1P)") (class "Default")
      (node (ref "C14") (pin "2") (pinfunction "2_2") (pintype "input"))
      (node (ref "IC1") (pin "13") (pinfunction "V1P_13") (pintype "unspecified"))
      (node (ref "IC1") (pin "15") (pinfunction "V2P_15") (pintype "unspecified"))
      (node (ref "IC1") (pin "17") (pinfunction "V3P_17") (pintype "unspecified"))
      (node (ref "R11") (pin "4") (pinfunction "4_4") (pintype "input"))
      (node (ref "R24") (pin "4") (pinfunction "4_4") (pintype "input"))
      (node (ref "R28") (pin "2") (pinfunction "2_2") (pintype "unspecified"))
    )
    (net (code "60") (name "Net-(IC1-Vref)") (class "Default")
      (node (ref "C12") (pin "1") (pinfunction "1_1") (pintype "input"))
      (node (ref "C13") (pin "2") (pinfunction "2_2") (pintype "unspecified"))
      (node (ref "IC1") (pin "11") (pinfunction "Vref_11") (pintype "unspecified"))
    )
    (net (code "61") (name "Net-(IC1-ZX0)") (class "Default")
      (node (ref "IC1") (pin "22") (pinfunction "ZX0_22") (pintype "unspecified"))
      (node (ref "ZX0") (pin "1") (pinfunction "Pad_1") (pintype "unspecified"))
    )
    (net (code "62") (name "Net-(IC1-ZX1)") (class "Default")
      (node (ref "IC1") (pin "23") (pinfunction "ZX1_23") (pintype "unspecified"))
      (node (ref "ZX1") (pin "1") (pinfunction "Pad_1") (pintype "unspecified"))
    )
    (net (code "63") (name "Net-(IC1-ZX2)") (class "Default")
      (node (ref "IC1") (pin "24") (pinfunction "ZX2_24") (pintype "unspecified"))
      (node (ref "ZX2") (pin "1") (pinfunction "Pad_1") (pintype "unspecified"))
    )
    (net (code "64") (name "Net-(IC2-CF1)") (class "Default")
      (node (ref "IC2") (pin "25") (pinfunction "CF1_25") (pintype "unspecified"))
      (node (ref "R20") (pin "2") (pinfunction "2_2") (pintype "input"))
    )
    (net (code "65") (name "Net-(IC2-CF2)") (class "Default")
      (node (ref "CF2-2") (pin "1") (pinfunction "Pad_1") (pintype "unspecified"))
      (node (ref "IC2") (pin "26") (pinfunction "CF2_26") (pintype "unspecified"))
    )
    (net (code "66") (name "Net-(IC2-CF3)") (class "Default")
      (node (ref "CF3-2") (pin "1") (pinfunction "Pad_1") (pintype "unspecified"))
      (node (ref "IC2") (pin "27") (pinfunction "CF3_27") (pintype "unspecified"))
    )
    (net (code "67") (name "Net-(IC2-CF4)") (class "Default")
      (node (ref "CF4-2") (pin "1") (pinfunction "Pad_1") (pintype "unspecified"))
      (node (ref "IC2") (pin "28") (pinfunction "CF4_28") (pintype "unspecified"))
    )
    (net (code "68") (name "Net-(IC2-I1N)") (class "Default")
      (node (ref "C18") (pin "2") (pinfunction "2_2") (pintype "unspecified"))
      (node (ref "IC2") (pin "4") (pinfunction "I1N_4") (pintype "unspecified"))
      (node (ref "R14") (pin "8") (pinfunction "8_8") (pintype "input"))
    )
    (net (code "69") (name "Net-(IC2-I1P)") (class "Default")
      (node (ref "C17") (pin "1") (pinfunction "1_1") (pintype "unspecified"))
      (node (ref "IC2") (pin "3") (pinfunction "I1P_3") (pintype "unspecified"))
      (node (ref "R14") (pin "7") (pinfunction "7_7") (pintype "input"))
    )
    (net (code "70") (name "Net-(IC2-I2N)") (class "Default")
      (node (ref "C20") (pin "2") (pinfunction "2_2") (pintype "unspecified"))
      (node (ref "IC2") (pin "6") (pinfunction "I2N_6") (pintype "unspecified"))
      (node (ref "R14") (pin "6") (pinfunction "6_6") (pintype "input"))
    )
    (net (code "71") (name "Net-(IC2-I2P)") (class "Default")
      (node (ref "C19") (pin "1") (pinfunction "1_1") (pintype "unspecified"))
      (node (ref "IC2") (pin "5") (pinfunction "I2P_5") (pintype "unspecified"))
      (node (ref "R14") (pin "5") (pinfunction "5_5") (pintype "input"))
    )
    (net (code "72") (name "Net-(IC2-I3N)") (class "Default")
      (node (ref "C22") (pin "1") (pinfunction "1_1") (pintype "unspecified"))
      (node (ref "IC2") (pin "8") (pinfunction "I3N_8") (pintype "unspecified"))
      (node (ref "R16") (pin "2") (pinfunction "2_2") (pintype "input"))
    )
    (net (code "73") (name "Net-(IC2-I3P)") (class "Default")
      (node (ref "C21") (pin "2") (pinfunction "2_2") (pintype "unspecified"))
      (node (ref "IC2") (pin "7") (pinfunction "I3P_7") (pintype "unspecified"))
      (node (ref "R15") (pin "2") (pinfunction "2_2") (pintype "input"))
    )
    (net (code "74") (name "Net-(IC2-OSCI)") (class "Default")
      (node (ref "IC2") (pin "20") (pinfunction "OSCI_20") (pintype "unspecified"))
      (node (ref "X2") (pin "3") (pinfunction "OSC2_3") (pintype "unspecified"))
    )
    (net (code "75") (name "Net-(IC2-OSCO)") (class "Default")
      (node (ref "IC2") (pin "21") (pinfunction "OSCO_21") (pintype "unspecified"))
      (node (ref "X2") (pin "1") (pinfunction "OSC1_1") (pintype "unspecified"))
    )
    (net (code "76") (name "Net-(IC2-RESET#)") (class "Default")
      (node (ref "C16") (pin "2") (pinfunction "2_2") (pintype "unspecified"))
      (node (ref "IC2") (pin "41") (pinfunction "RESET#_41") (pintype "unspecified"))
      (node (ref "R12") (pin "1") (pinfunction "1_1") (pintype "unspecified"))
    )
    (net (code "77") (name "Net-(IC2-V1N)") (class "Default")
      (node (ref "C30") (pin "2") (pinfunction "2_2") (pintype "input"))
      (node (ref "IC2") (pin "14") (pinfunction "V1N_14") (pintype "unspecified"))
      (node (ref "IC2") (pin "16") (pinfunction "V2N_16") (pintype "unspecified"))
      (node (ref "IC2") (pin "18") (pinfunction "V3N_18") (pintype "unspecified"))
      (node (ref "R11") (pin "2") (pinfunction "2_2") (pintype "input"))
      (node (ref "R24") (pin "2") (pinfunction "2_2") (pintype "input"))
      (node (ref "R34") (pin "2") (pinfunction "2_2") (pintype "unspecified"))
    )
    (net (code "78") (name "Net-(IC2-V1P)") (class "Default")
      (node (ref "C29") (pin "2") (pinfunction "2_2") (pintype "input"))
      (node (ref "IC2") (pin "13") (pinfunction "V1P_13") (pintype "unspecified"))
      (node (ref "IC2") (pin "15") (pinfunction "V2P_15") (pintype "unspecified"))
      (node (ref "IC2") (pin "17") (pinfunction "V3P_17") (pintype "unspecified"))
      (node (ref "R11") (pin "3") (pinfunction "3_3") (pintype "input"))
      (node (ref "R24") (pin "3") (pinfunction "3_3") (pintype "input"))
      (node (ref "R26") (pin "2") (pinfunction "2_2") (pintype "unspecified"))
    )
    (net (code "79") (name "Net-(IC2-Vref)") (class "Default")
      (node (ref "C27") (pin "1") (pinfunction "1_1") (pintype "input"))
      (node (ref "C28") (pin "2") (pinfunction "2_2") (pintype "unspecified"))
      (node (ref "IC2") (pin "11") (pinfunction "Vref_11") (pintype "unspecified"))
    )
    (net (code "80") (name "Net-(IC2-ZX0)") (class "Default")
      (node (ref "IC2") (pin "22") (pinfunction "ZX0_22") (pintype "unspecified"))
      (node (ref "ZX3") (pin "1") (pinfunction "Pad_1") (pintype "unspecified"))
    )
    (net (code "81") (name "Net-(IC2-ZX1)") (class "Default")
      (node (ref "IC2") (pin "23") (pinfunction "ZX1_23") (pintype "unspecified"))
      (node (ref "ZX4") (pin "1") (pinfunction "Pad_1") (pintype "unspecified"))
    )
    (net (code "82") (name "Net-(IC2-ZX2)") (class "Default")
      (node (ref "IC2") (pin "24") (pinfunction "ZX2_24") (pintype "unspecified"))
      (node (ref "ZX5") (pin "1") (pinfunction "Pad_1") (pintype "unspecified"))
    )
    (net (code "83") (name "Net-(IC3-BOOT)") (class "Default")
      (node (ref "C31") (pin "2") (pinfunction "2_2") (pintype "unspecified"))
      (node (ref "IC3") (pin "1") (pinfunction "BOOT_1") (pintype "unspecified"))
    )
    (net (code "84") (name "Net-(IC3-FB)") (class "Default")
      (node (ref "C32") (pin "1") (pinfunction "1_1") (pintype "unspecified"))
      (node (ref "IC3") (pin "5") (pinfunction "FB_5") (pintype "unspecified"))
      (node (ref "R22") (pin "1") (pinfunction "1_1") (pintype "unspecified"))
      (node (ref "R23") (pin "2") (pinfunction "2_2") (pintype "unspecified"))
    )
    (net (code "85") (name "Net-(IC3-RT{slash}SYNC)") (class "Default")
      (node (ref "IC3") (pin "4") (pinfunction "RT/SYNC_4") (pintype "unspecified"))
      (node (ref "R21") (pin "2") (pinfunction "2_2") (pintype "unspecified"))
    )
    (net (code "86") (name "Net-(IC3-SS)") (class "Default")
      (node (ref "C35") (pin "2") (pinfunction "2_2") (pintype "input"))
      (node (ref "IC3") (pin "6") (pinfunction "SS_6") (pintype "unspecified"))
    )
    (net (code "87") (name "Net-(JP1-Pad1)") (class "Default")
      (node (ref "JP1") (pin "1") (pinfunction "1_1") (pintype "unspecified"))
      (node (ref "R7") (pin "1") (pinfunction "1_1") (pintype "unspecified"))
    )
    (net (code "88") (name "Net-(JP2-Pad1)") (class "Default")
      (node (ref "JP2") (pin "1") (pinfunction "1_1") (pintype "unspecified"))
      (node (ref "R8") (pin "1") (pinfunction "1_1") (pintype "unspecified"))
    )
    (net (code "89") (name "Net-(JP3-Pad1)") (class "Default")
      (node (ref "JP3") (pin "1") (pinfunction "1_1") (pintype "unspecified"))
      (node (ref "R6") (pin "1") (pinfunction "1_1") (pintype "unspecified"))
    )
    (net (code "90") (name "Net-(JP4-Pad1)") (class "Default")
      (node (ref "JP4") (pin "1") (pinfunction "1_1") (pintype "unspecified"))
      (node (ref "R18") (pin "1") (pinfunction "1_1") (pintype "unspecified"))
    )
    (net (code "91") (name "Net-(JP5-Pad1)") (class "Default")
      (node (ref "JP5") (pin "1") (pinfunction "1_1") (pintype "unspecified"))
      (node (ref "R19") (pin "1") (pinfunction "1_1") (pintype "unspecified"))
    )
    (net (code "92") (name "Net-(JP6-Pad1)") (class "Default")
      (node (ref "JP6") (pin "1") (pinfunction "1_1") (pintype "unspecified"))
      (node (ref "R17") (pin "1") (pinfunction "1_1") (pintype "unspecified"))
    )
    (net (code "93") (name "Net-(JP12-Pad2)") (class "Default")
      (node (ref "JP12") (pin "2") (pinfunction "2_2") (pintype "unspecified"))
      (node (ref "R28") (pin "1") (pinfunction "1_1") (pintype "unspecified"))
      (node (ref "VA2+") (pin "1") (pinfunction "Pad_1") (pintype "unspecified"))
    )
    (net (code "94") (name "Net-(JP13-Pad1)") (class "Default")
      (node (ref "JP13") (pin "1") (pinfunction "1_1") (pintype "unspecified"))
      (node (ref "R32") (pin "1") (pinfunction "1_1") (pintype "unspecified"))
      (node (ref "VA2-") (pin "1") (pinfunction "Pad_1") (pintype "unspecified"))
    )
    (net (code "95") (name "Net-(PWR-A)") (class "Default")
      (node (ref "PWR") (pin "1") (pinfunction "A_1") (pintype "unspecified"))
      (node (ref "R10") (pin "1") (pinfunction "1_1") (pintype "unspecified"))
    )
    (net (code "96") (name "VCC") (class "Default")
      (node (ref "3V3") (pin "1") (pinfunction "Pad_1") (pintype "unspecified"))
      (node (ref "C10") (pin "2") (pinfunction "2_2") (pintype "unspecified"))
      (node (ref "C11") (pin "2") (pinfunction "2_2") (pintype "unspecified"))
      (node (ref "C25") (pin "2") (pinfunction "2_2") (pintype "unspecified"))
      (node (ref "C26") (pin "2") (pinfunction "2_2") (pintype "unspecified"))
      (node (ref "C32") (pin "2") (pinfunction "2_2") (pintype "unspecified"))
      (node (ref "C36") (pin "2") (pinfunction "2_2") (pintype "unspecified"))
      (node (ref "ESP32") (pin "1") (pinfunction "3V3_1") (pintype "bidirectional"))
      (node (ref "IC1") (pin "1") (pinfunction "AVDD_1") (pintype "unspecified"))
      (node (ref "IC1") (pin "33") (pinfunction "PM0_33") (pintype "unspecified"))
      (node (ref "IC1") (pin "34") (pinfunction "PM1_34") (pintype "unspecified"))
      (node (ref "IC1") (pin "48") (pinfunction "DVDD_48") (pintype "unspecified"))
      (node (ref "IC2") (pin "1") (pinfunction "AVDD_1") (pintype "unspecified"))
      (node (ref "IC2") (pin "33") (pinfunction "PM0_33") (pintype "unspecified"))
      (node (ref "IC2") (pin "34") (pinfunction "PM1_34") (pintype "unspecified"))
      (node (ref "IC2") (pin "48") (pinfunction "DVDD_48") (pintype "unspecified"))
      (node (ref "L1") (pin "2") (pinfunction "2_2") (pintype "unspecified"))
      (node (ref "R1") (pin "2") (pinfunction "2_2") (pintype "unspecified"))
      (node (ref "R10") (pin "2") (pinfunction "2_2") (pintype "unspecified"))
      (node (ref "R12") (pin "2") (pinfunction "2_2") (pintype "unspecified"))
      (node (ref "R13") (pin "2") (pinfunction "2_2") (pintype "unspecified"))
      (node (ref "R2") (pin "5") (pinfunction "5_5") (pintype "input"))
      (node (ref "R2") (pin "6") (pinfunction "6_6") (pintype "input"))
      (node (ref "R2") (pin "7") (pinfunction "7_7") (pintype "input"))
      (node (ref "R2") (pin "8") (pinfunction "8_8") (pintype "input"))
      (node (ref "R22") (pin "2") (pinfunction "2_2") (pintype "unspecified"))
      (node (ref "R24") (pin "5") (pinfunction "5_5") (pintype "input"))
      (node (ref "R24") (pin "6") (pinfunction "6_6") (pintype "input"))
      (node (ref "R24") (pin "7") (pinfunction "7_7") (pintype "input"))
      (node (ref "R24") (pin "8") (pinfunction "8_8") (pintype "input"))
      (node (ref "R27") (pin "2") (pinfunction "2_2") (pintype "unspecified"))
    )
    (net (code "97") (name "unconnected-(AC-Pad3)") (class "Default")
      (node (ref "AC") (pin "3") (pinfunction "3_3") (pintype "unspecified"))
    )
    (net (code "98") (name "unconnected-(CT1-Pad2)") (class "Default")
      (node (ref "CT1") (pin "2") (pinfunction "2_2") (pintype "unspecified+no_connect"))
    )
    (net (code "99") (name "unconnected-(CT1-Pad3)") (class "Default")
      (node (ref "CT1") (pin "3") (pinfunction "3_3") (pintype "unspecified+no_connect"))
    )
    (net (code "100") (name "unconnected-(CT2-Pad2)") (class "Default")
      (node (ref "CT2") (pin "2") (pinfunction "2_2") (pintype "unspecified+no_connect"))
    )
    (net (code "101") (name "unconnected-(CT2-Pad3)") (class "Default")
      (node (ref "CT2") (pin "3") (pinfunction "3_3") (pintype "unspecified+no_connect"))
    )
    (net (code "102") (name "unconnected-(CT3-Pad2)") (class "Default")
      (node (ref "CT3") (pin "2") (pinfunction "2_2") (pintype "unspecified+no_connect"))
    )
    (net (code "103") (name "unconnected-(CT3-Pad3)") (class "Default")
      (node (ref "CT3") (pin "3") (pinfunction "3_3") (pintype "unspecified+no_connect"))
    )
    (net (code "104") (name "unconnected-(CT4-Pad2)") (class "Default")
      (node (ref "CT4") (pin "2") (pinfunction "2_2") (pintype "unspecified+no_connect"))
    )
    (net (code "105") (name "unconnected-(CT4-Pad3)") (class "Default")
      (node (ref "CT4") (pin "3") (pinfunction "3_3") (pintype "unspecified+no_connect"))
    )
    (net (code "106") (name "unconnected-(CT5-Pad2)") (class "Default")
      (node (ref "CT5") (pin "2") (pinfunction "2_2") (pintype "unspecified+no_connect"))
    )
    (net (code "107") (name "unconnected-(CT5-Pad3)") (class "Default")
      (node (ref "CT5") (pin "3") (pinfunction "3_3") (pintype "unspecified+no_connect"))
    )
    (net (code "108") (name "unconnected-(CT6-Pad2)") (class "Default")
      (node (ref "CT6") (pin "2") (pinfunction "2_2") (pintype "unspecified+no_connect"))
    )
    (net (code "109") (name "unconnected-(CT6-Pad3)") (class "Default")
      (node (ref "CT6") (pin "3") (pinfunction "3_3") (pintype "unspecified+no_connect"))
    )
    (net (code "110") (name "unconnected-(ESP32-CLK-Pad38)") (class "Default")
      (node (ref "ESP32") (pin "38") (pinfunction "CLK_38") (pintype "bidirectional+no_connect"))
    )
    (net (code "111") (name "unconnected-(ESP32-CMD-Pad18)") (class "Default")
      (node (ref "ESP32") (pin "18") (pinfunction "CMD_18") (pintype "bidirectional+no_connect"))
    )
    (net (code "112") (name "unconnected-(ESP32-EN-Pad2)") (class "Default")
      (node (ref "ESP32") (pin "2") (pinfunction "EN_2") (pintype "bidirectional+no_connect"))
    )
    (net (code "113") (name "unconnected-(ESP32-EXT_5V-Pad19)") (class "Default")
      (node (ref "ESP32") (pin "19") (pinfunction "EXT_5V_19") (pintype "bidirectional+no_connect"))
    )
    (net (code "114") (name "unconnected-(ESP32-RXD0-Pad24)") (class "Default")
      (node (ref "ESP32") (pin "24") (pinfunction "RXD0_24") (pintype "bidirectional+no_connect"))
    )
    (net (code "115") (name "unconnected-(ESP32-SD0-Pad37)") (class "Default")
      (node (ref "ESP32") (pin "37") (pinfunction "SD0_37") (pintype "bidirectional+no_connect"))
    )
    (net (code "116") (name "unconnected-(ESP32-SD1-Pad36)") (class "Default")
      (node (ref "ESP32") (pin "36") (pinfunction "SD1_36") (pintype "bidirectional+no_connect"))
    )
    (net (code "117") (name "unconnected-(ESP32-SD2-Pad16)") (class "Default")
      (node (ref "ESP32") (pin "16") (pinfunction "SD2_16") (pintype "bidirectional+no_connect"))
    )
    (net (code "118") (name "unconnected-(ESP32-SD3-Pad17)") (class "Default")
      (node (ref "ESP32") (pin "17") (pinfunction "SD3_17") (pintype "bidirectional+no_connect"))
    )
    (net (code "119") (name "unconnected-(ESP32-SENSOR_VN-Pad4)") (class "Default")
      (node (ref "ESP32") (pin "4") (pinfunction "SENSOR_VN_4") (pintype "bidirectional+no_connect"))
    )
    (net (code "120") (name "unconnected-(ESP32-TXD0-Pad23)") (class "Default")
      (node (ref "ESP32") (pin "23") (pinfunction "TXD0_23") (pintype "bidirectional+no_connect"))
    )
    (net (code "121") (name "unconnected-(IC1-IC-Pad9)") (class "Default")
      (node (ref "IC1") (pin "9") (pinfunction "IC_9") (pintype "unspecified+no_connect"))
    )
    (net (code "122") (name "unconnected-(IC1-IC-Pad10)") (class "Default")
      (node (ref "IC1") (pin "10") (pinfunction "IC_10") (pintype "unspecified+no_connect"))
    )
    (net (code "123") (name "unconnected-(IC1-NC-Pad35)") (class "Default")
      (node (ref "IC1") (pin "35") (pinfunction "NC_35") (pintype "unspecified+no_connect"))
    )
    (net (code "124") (name "unconnected-(IC1-NC-Pad45)") (class "Default")
      (node (ref "IC1") (pin "45") (pinfunction "NC_45") (pintype "unspecified+no_connect"))
    )
    (net (code "125") (name "unconnected-(IC1-NC-Pad46)") (class "Default")
      (node (ref "IC1") (pin "46") (pinfunction "NC_46") (pintype "unspecified+no_connect"))
    )
    (net (code "126") (name "unconnected-(IC2-IC-Pad9)") (class "Default")
      (node (ref "IC2") (pin "9") (pinfunction "IC_9") (pintype "unspecified+no_connect"))
    )
    (net (code "127") (name "unconnected-(IC2-IC-Pad10)") (class "Default")
      (node (ref "IC2") (pin "10") (pinfunction "IC_10") (pintype "unspecified+no_connect"))
    )
    (net (code "128") (name "unconnected-(IC2-NC-Pad35)") (class "Default")
      (node (ref "IC2") (pin "35") (pinfunction "NC_35") (pintype "unspecified+no_connect"))
    )
    (net (code "129") (name "unconnected-(IC2-NC-Pad45)") (class "Default")
      (node (ref "IC2") (pin "45") (pinfunction "NC_45") (pintype "unspecified+no_connect"))
    )
    (net (code "130") (name "unconnected-(IC2-NC-Pad46)") (class "Default")
      (node (ref "IC2") (pin "46") (pinfunction "NC_46") (pintype "unspecified+no_connect"))
    )
  )
)
